# Micro.net
KiCad netlist of a schematic drawn in Altium Designer
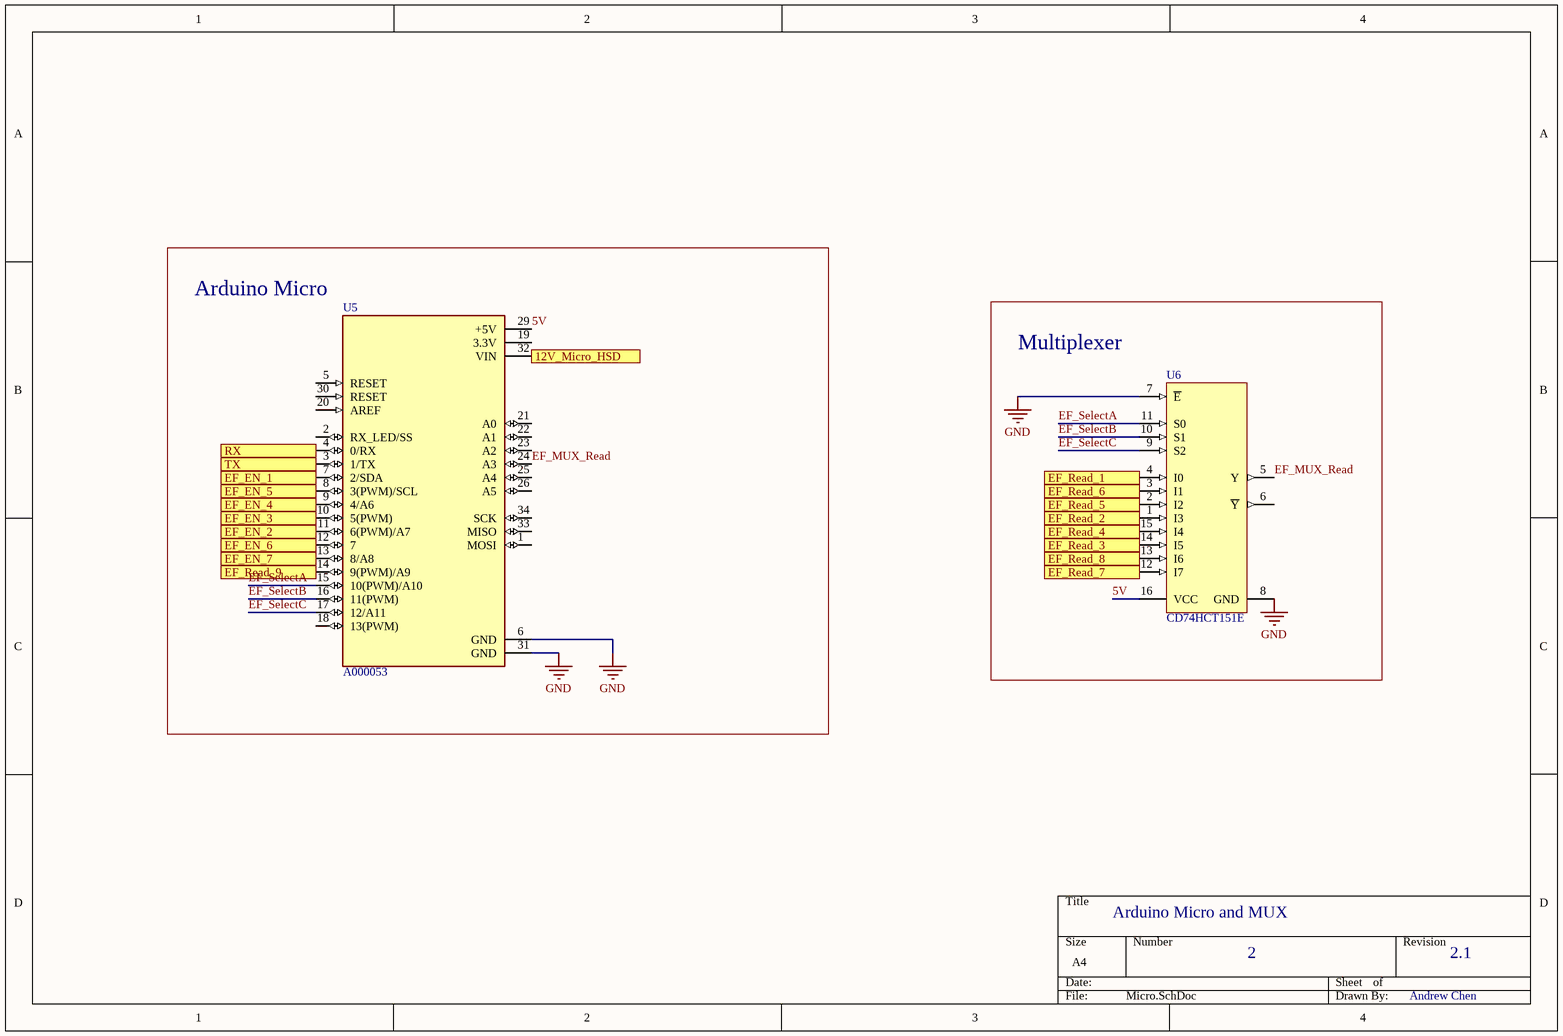
[diagram p0: Micro.SchDoc]

(export (version "E")
  (design (tool "Eeschema 10.0.6"))
  (components
    (comp (ref "U5")
      (value "A000053")
      (footprint "ARDUINO_A000053")
      (description "ATmega32U4 Arduino Micro AVRÂ® ATmega AVR MCU 8-Bit Embedded Evaluation Board")
      (fields (field (name "DIGI-KEY_PART_NUMBER") "1050-1066-ND") (field (name "MF") "Arduino"))
      (libsource (lib "SnapEDAsch") (part "A000053"))
    )
    (comp (ref "U6")
      (value "CD74HCT151E")
      (footprint "N0016A")
      (description "High Speed CMOS Logic 8-Input Multiplexer, N0016A, TUBE")
      (fields
        (field (name "MANUFACTURER") "Texas Instruments")
        (field (name "GENERIC PART NUMBER") "CD74HCT151")
      )
      (libsource (lib "Altium Content Vault") (part "TI-CDX4HCX151-16"))
    )
  )
  (nets
    (net (code "1") (name "/5V") (class "Default")
      (node (ref "U5") (pin "29") (pinfunction "+5V_29") (pintype "power_in"))
      (node (ref "U6") (pin "16") (pinfunction "VCC_16") (pintype "power_in"))
    )
    (net (code "2") (name "/12V_Micro_HSD") (class "Default")
      (node (ref "U5") (pin "32") (pinfunction "VIN_32") (pintype "power_in"))
    )
    (net (code "3") (name "/EF_EN_1") (class "Default")
      (node (ref "U5") (pin "7") (pinfunction "2/SDA_7") (pintype "bidirectional"))
    )
    (net (code "4") (name "/EF_EN_2") (class "Default")
      (node (ref "U5") (pin "11") (pinfunction "6(PWM)/A7_11") (pintype "bidirectional"))
    )
    (net (code "5") (name "/EF_EN_3") (class "Default")
      (node (ref "U5") (pin "10") (pinfunction "5(PWM)_10") (pintype "bidirectional"))
    )
    (net (code "6") (name "/EF_EN_4") (class "Default")
      (node (ref "U5") (pin "9") (pinfunction "4/A6_9") (pintype "bidirectional"))
    )
    (net (code "7") (name "/EF_EN_5") (class "Default")
      (node (ref "U5") (pin "8") (pinfunction "3(PWM)/SCL_8") (pintype "bidirectional"))
    )
    (net (code "8") (name "/EF_EN_6") (class "Default")
      (node (ref "U5") (pin "12") (pinfunction "7_12") (pintype "bidirectional"))
    )
    (net (code "9") (name "/EF_EN_7") (class "Default")
      (node (ref "U5") (pin "13") (pinfunction "8/A8_13") (pintype "bidirectional"))
    )
    (net (code "10") (name "/EF_MUX_Read") (class "Default")
      (node (ref "U5") (pin "24") (pinfunction "A3_24") (pintype "bidirectional"))
      (node (ref "U6") (pin "5") (pinfunction "Y_5") (pintype "output"))
    )
    (net (code "11") (name "/EF_Read_1") (class "Default")
      (node (ref "U6") (pin "4") (pinfunction "I0_4") (pintype "input"))
    )
    (net (code "12") (name "/EF_Read_2") (class "Default")
      (node (ref "U6") (pin "1") (pinfunction "I3_1") (pintype "input"))
    )
    (net (code "13") (name "/EF_Read_3") (class "Default")
      (node (ref "U6") (pin "14") (pinfunction "I5_14") (pintype "input"))
    )
    (net (code "14") (name "/EF_Read_4") (class "Default")
      (node (ref "U6") (pin "15") (pinfunction "I4_15") (pintype "input"))
    )
    (net (code "15") (name "/EF_Read_5") (class "Default")
      (node (ref "U6") (pin "2") (pinfunction "I2_2") (pintype "input"))
    )
    (net (code "16") (name "/EF_Read_6") (class "Default")
      (node (ref "U6") (pin "3") (pinfunction "I1_3") (pintype "input"))
    )
    (net (code "17") (name "/EF_Read_7") (class "Default")
      (node (ref "U6") (pin "12") (pinfunction "I7_12") (pintype "input"))
    )
    (net (code "18") (name "/EF_Read_8") (class "Default")
      (node (ref "U6") (pin "13") (pinfunction "I6_13") (pintype "input"))
    )
    (net (code "19") (name "/EF_Read_9") (class "Default")
      (node (ref "U5") (pin "14") (pinfunction "9(PWM)/A9_14") (pintype "bidirectional"))
    )
    (net (code "20") (name "/EF_SelectA") (class "Default")
      (node (ref "U5") (pin "15") (pinfunction "10(PWM)/A10_15") (pintype "bidirectional"))
      (node (ref "U6") (pin "11") (pinfunction "S0_11") (pintype "input"))
    )
    (net (code "21") (name "/EF_SelectB") (class "Default")
      (node (ref "U5") (pin "16") (pinfunction "11(PWM)_16") (pintype "bidirectional"))
      (node (ref "U6") (pin "10") (pinfunction "S1_10") (pintype "input"))
    )
    (net (code "22") (name "/EF_SelectC") (class "Default")
      (node (ref "U5") (pin "17") (pinfunction "12/A11_17") (pintype "bidirectional"))
      (node (ref "U6") (pin "9") (pinfunction "S2_9") (pintype "input"))
    )
    (net (code "23") (name "/RX") (class "Default")
      (node (ref "U5") (pin "4") (pinfunction "0/RX_4") (pintype "bidirectional"))
    )
    (net (code "24") (name "/TX") (class "Default")
      (node (ref "U5") (pin "3") (pinfunction "1/TX_3") (pintype "bidirectional"))
    )
    (net (code "25") (name "GND") (class "Default")
      (node (ref "U5") (pin "31") (pinfunction "GND_31") (pintype "power_in"))
      (node (ref "U5") (pin "6") (pinfunction "GND_6") (pintype "power_in"))
      (node (ref "U6") (pin "7") (pinfunction "~{E}_7") (pintype "input"))
      (node (ref "U6") (pin "8") (pinfunction "GND_8") (pintype "power_in"))
    )
    (net (code "26") (name "unconnected-(U5-3.3V-Pad19)") (class "Default")
      (node (ref "U5") (pin "19") (pinfunction "3.3V_19") (pintype "power_in"))
    )
    (net (code "27") (name "unconnected-(U5-13(PWM)-Pad18)") (class "Default")
      (node (ref "U5") (pin "18") (pinfunction "13(PWM)_18") (pintype "bidirectional"))
    )
    (net (code "28") (name "unconnected-(U5-A0-Pad21)") (class "Default")
      (node (ref "U5") (pin "21") (pinfunction "A0_21") (pintype "bidirectional"))
    )
    (net (code "29") (name "unconnected-(U5-A1-Pad22)") (class "Default")
      (node (ref "U5") (pin "22") (pinfunction "A1_22") (pintype "bidirectional"))
    )
    (net (code "30") (name "unconnected-(U5-A2-Pad23)") (class "Default")
      (node (ref "U5") (pin "23") (pinfunction "A2_23") (pintype "bidirectional"))
    )
    (net (code "31") (name "unconnected-(U5-A4-Pad25)") (class "Default")
      (node (ref "U5") (pin "25") (pinfunction "A4_25") (pintype "bidirectional"))
    )
    (net (code "32") (name "unconnected-(U5-A5-Pad26)") (class "Default")
      (node (ref "U5") (pin "26") (pinfunction "A5_26") (pintype "bidirectional"))
    )
    (net (code "33") (name "unconnected-(U5-AREF-Pad20)") (class "Default")
      (node (ref "U5") (pin "20") (pinfunction "AREF_20") (pintype "input"))
    )
    (net (code "34") (name "unconnected-(U5-MISO-Pad33)") (class "Default")
      (node (ref "U5") (pin "33") (pinfunction "MISO_33") (pintype "bidirectional"))
    )
    (net (code "35") (name "unconnected-(U5-MOSI-Pad1)") (class "Default")
      (node (ref "U5") (pin "1") (pinfunction "MOSI_1") (pintype "bidirectional"))
    )
    (net (code "36") (name "unconnected-(U5-RESET-Pad5)") (class "Default")
      (node (ref "U5") (pin "5") (pinfunction "RESET_5") (pintype "input"))
    )
    (net (code "37") (name "unconnected-(U5-RESET-Pad30)") (class "Default")
      (node (ref "U5") (pin "30") (pinfunction "RESET_30") (pintype "input"))
    )
    (net (code "38") (name "unconnected-(U5-RX_LED{slash}SS-Pad2)") (class "Default")
      (node (ref "U5") (pin "2") (pinfunction "RX_LED/SS_2") (pintype "bidirectional"))
    )
    (net (code "39") (name "unconnected-(U5-SCK-Pad34)") (class "Default")
      (node (ref "U5") (pin "34") (pinfunction "SCK_34") (pintype "bidirectional"))
    )
    (net (code "40") (name "unconnected-(U6-~{Y}-Pad6)") (class "Default")
      (node (ref "U6") (pin "6") (pinfunction "~{Y}_6") (pintype "output"))
    )
  )
)
